# CPUWroom_Schem.net
KiCad netlist of a schematic drawn in Altium Designer
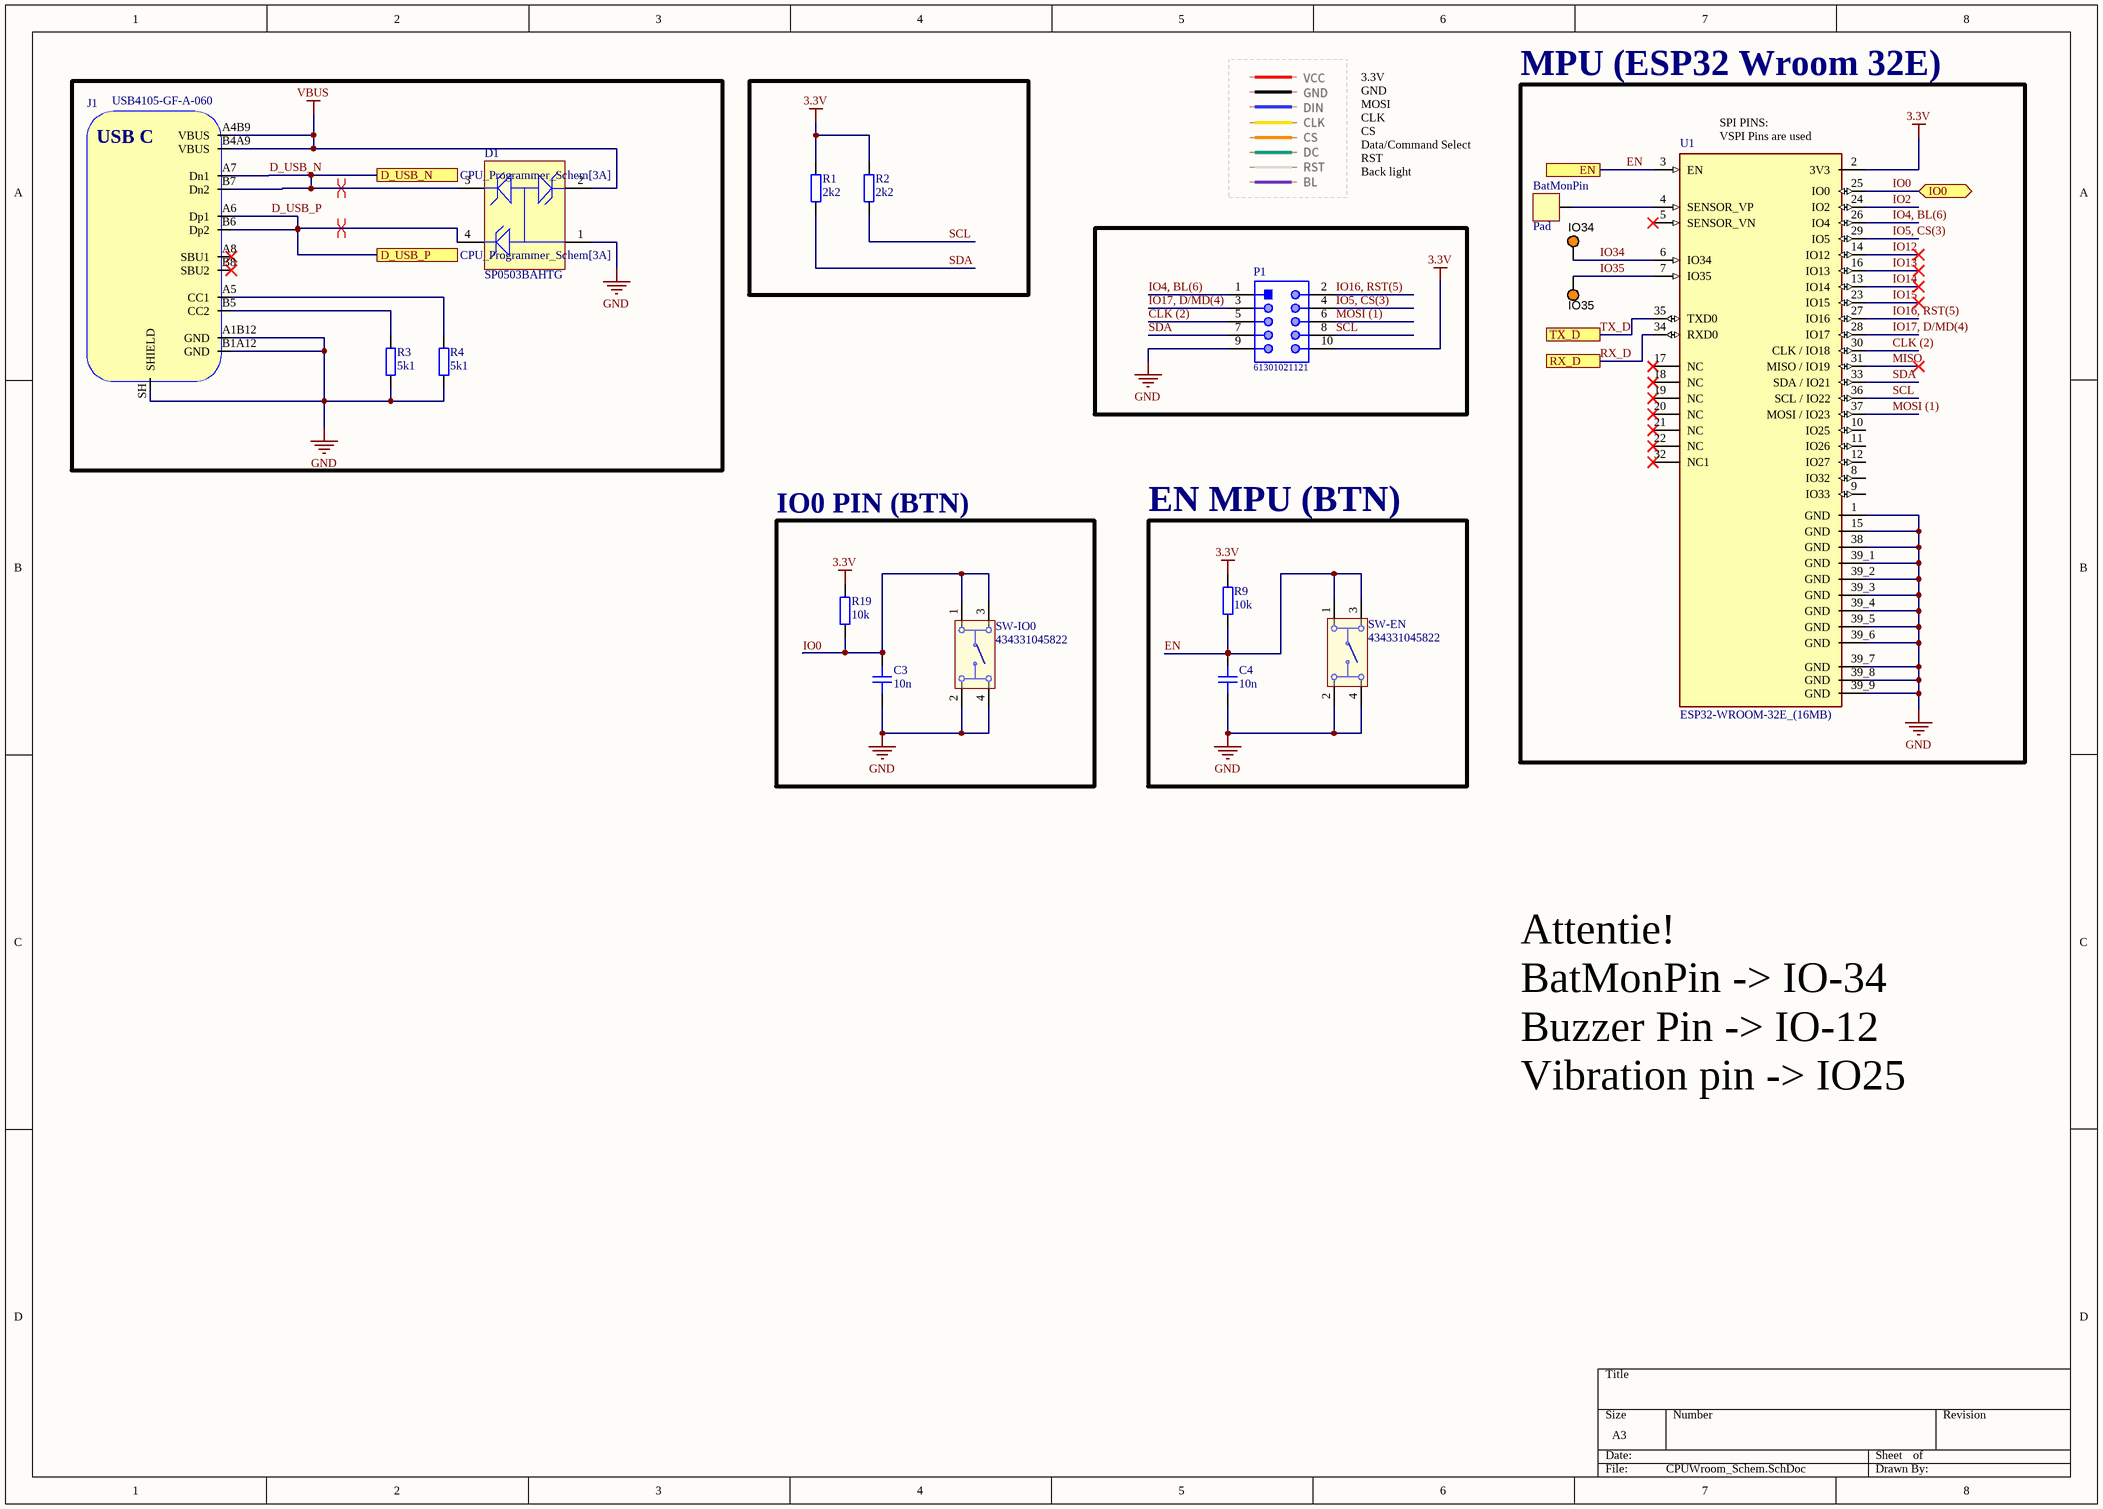
[diagram p0: CPUWroom_Schem.SchDoc]

(export (version "E")
  (design (tool "Eeschema 10.0.6"))
  (components
    (comp (ref "BatMonPin")
      (value "Pad")
      (footprint "PAD_SQ_2MM")
      (description "Test Point Square 2mm")
      (libsource (lib "Schem_Lib_DaanHeetkamp.") (part "PAD_SQ_2MM"))
    )
    (comp (ref "C3")
      (value "10n")
      (footprint "CAP_1206")
      (description "Capacitor SMD 1206 50V")
      (libsource (lib "Schem_Lib_DaanHeetkamp.") (part "CAP_1206_50V"))
    )
    (comp (ref "C4")
      (value "10n")
      (footprint "CAP_1206")
      (description "Capacitor SMD 1206 50V")
      (libsource (lib "Schem_Lib_DaanHeetkamp.") (part "CAP_1206_50V"))
    )
    (comp (ref "D1")
      (value "SP0503BAHTG")
      (footprint "LFUS-SOT143-4_V")
      (description "TVS Diode Array, 30 pF, 30 KV, -40 to 85 degC, 4-Pin SOT143, RoHS, Tape and Reel")
      (fields (field (name "MANUFACTURER") "Littelfuse"))
      (libsource (lib "Altium Content Vault") (part "LFUS-SP0503BAHTG-SOT143-4"))
    )
    (comp (ref "IO34")
      (value "5003")
      (footprint "KSTN-5003")
      (description "Test Point, Orange, Height 4.6 mm, Tail Length 3 mm, 1-Pin THD, RoHS")
      (fields (field (name "MANUFACTURER") "Keystone"))
      (libsource (lib "Saxion University of Applied Sciences") (part "TESTPOINT_ORANGE"))
    )
    (comp (ref "IO35")
      (value "5003")
      (footprint "KSTN-5003")
      (description "Test Point, Orange, Height 4.6 mm, Tail Length 3 mm, 1-Pin THD, RoHS")
      (fields (field (name "MANUFACTURER") "Keystone"))
      (libsource (lib "Saxion University of Applied Sciences") (part "TESTPOINT_ORANGE"))
    )
    (comp (ref "J1")
      (value "USB4105-GF-A-060")
      (footprint "USB4105-GF-A-060")
      (description "USB Connector Type C SMT 12 Pin")
      (fields (field (name "MANUFACTURER") "GCT"))
      (libsource (lib "Schem_Lib_DaanHeetkamp.") (part "USB4105-GF-A-060"))
    )
    (comp (ref "P1")
      (value "61301021121")
      (footprint "61301021121")
      (description "THT Vertical Pin Header WR-PHD, Pitch 2.54 mm, Dual Row, 10 pins")
      (fields (field (name "MANUFACTURER") "Wurth Elektronik") (field (name "PUBLISHER") "WurthElektronik"))
      (libsource (lib "Altium Content Vault") (part "WE-CN-2P-M-R10"))
    )
    (comp (ref "R1")
      (value "2k2")
      (footprint "RES_1206")
      (description "Resistor SMD 1206")
      (libsource (lib "Schem_Lib_DaanHeetkamp.") (part "RES_1206"))
    )
    (comp (ref "R2")
      (value "2k2")
      (footprint "RES_1206")
      (description "Resistor SMD 1206")
      (libsource (lib "Schem_Lib_DaanHeetkamp.") (part "RES_1206"))
    )
    (comp (ref "R3")
      (value "5k1")
      (footprint "RES_1206")
      (description "Resistor SMD 1206")
      (libsource (lib "Schem_Lib_DaanHeetkamp.") (part "RES_1206"))
    )
    (comp (ref "R4")
      (value "5k1")
      (footprint "RES_1206")
      (description "Resistor SMD 1206")
      (libsource (lib "Schem_Lib_DaanHeetkamp.") (part "RES_1206"))
    )
    (comp (ref "R9")
      (value "10k")
      (footprint "RES_1206")
      (description "Resistor SMD 1206")
      (libsource (lib "Schem_Lib_DaanHeetkamp.") (part "RES_1206"))
    )
    (comp (ref "R19")
      (value "10k")
      (footprint "RES_1206")
      (description "Resistor SMD 1206")
      (libsource (lib "Schem_Lib_DaanHeetkamp.") (part "RES_1206"))
    )
    (comp (ref "SW-EN")
      (value "434331045822")
      (footprint "434331045822")
      (description "WS-TASU SMD Tact Switch 4.7X3.5 mm side push")
      (fields (field (name "MANUFACTURER") "Wuerth Elektronik"))
      (libsource (lib "Altium Content Vault") (part "WE-TACT-SW-4"))
    )
    (comp (ref "SW-IO0")
      (value "434331045822")
      (footprint "434331045822")
      (description "WS-TASU SMD Tact Switch 4.7X3.5 mm side push")
      (fields (field (name "MANUFACTURER") "Wuerth Elektronik"))
      (libsource (lib "Altium Content Vault") (part "WE-TACT-SW-4"))
    )
    (comp (ref "U1")
      (value "ESP32-WROOM-32E_(16MB)")
      (footprint "XCVR_ESP32-WROOM-32E_(16MB)")
      (fields (field (name "MP") "ESP32-WROOM-32E (16MB)") (field (name "MF") "Espressif Systems"))
      (libsource (lib "Schem_Lib_DaanHeetkamp.") (part "ESP32-WROOM-32E_(16MB)"))
    )
  )
  (nets
    (net (code "1") (name "/CLK (2)") (class "Default")
      (node (ref "P1") (pin "5") (pinfunction "5_5") (pintype "passive"))
      (node (ref "U1") (pin "30") (pinfunction "CLK_/_IO18_30") (pintype "bidirectional"))
    )
    (net (code "2") (name "/D_USB_N") (class "Default")
      (node (ref "D1") (pin "3") (pinfunction "3_3") (pintype "passive"))
      (node (ref "J1") (pin "A7") (pinfunction "Dn1_A7") (pintype "passive"))
      (node (ref "J1") (pin "B7") (pinfunction "Dn2_B7") (pintype "passive"))
    )
    (net (code "3") (name "/D_USB_P") (class "Default")
      (node (ref "D1") (pin "4") (pinfunction "4_4") (pintype "passive"))
      (node (ref "J1") (pin "A6") (pinfunction "Dp1_A6") (pintype "passive"))
      (node (ref "J1") (pin "B6") (pinfunction "Dp2_B6") (pintype "passive"))
    )
    (net (code "4") (name "/EN") (class "Default")
      (node (ref "C4") (pin "2") (pinfunction "2_2") (pintype "passive"))
      (node (ref "R9") (pin "2") (pinfunction "2_2") (pintype "passive"))
      (node (ref "SW-EN") (pin "1") (pinfunction "1_1") (pintype "passive"))
      (node (ref "SW-EN") (pin "3") (pinfunction "3_3") (pintype "passive"))
      (node (ref "U1") (pin "3") (pinfunction "EN_3") (pintype "input"))
    )
    (net (code "5") (name "/IO0") (class "Default")
      (node (ref "C3") (pin "2") (pinfunction "2_2") (pintype "passive"))
      (node (ref "R19") (pin "2") (pinfunction "2_2") (pintype "passive"))
      (node (ref "SW-IO0") (pin "1") (pinfunction "1_1") (pintype "passive"))
      (node (ref "SW-IO0") (pin "3") (pinfunction "3_3") (pintype "passive"))
      (node (ref "U1") (pin "25") (pinfunction "IO0_25") (pintype "bidirectional"))
    )
    (net (code "6") (name "/IO2") (class "Default")
      (node (ref "U1") (pin "24") (pinfunction "IO2_24") (pintype "bidirectional"))
    )
    (net (code "7") (name "/IO4, BL(6)") (class "Default")
      (node (ref "P1") (pin "1") (pinfunction "1_1") (pintype "passive"))
      (node (ref "U1") (pin "26") (pinfunction "IO4_26") (pintype "bidirectional"))
    )
    (net (code "8") (name "/IO5, CS(3)") (class "Default")
      (node (ref "P1") (pin "4") (pinfunction "4_4") (pintype "passive"))
      (node (ref "U1") (pin "29") (pinfunction "IO5_29") (pintype "bidirectional"))
    )
    (net (code "9") (name "/IO12") (class "Default")
      (node (ref "U1") (pin "14") (pinfunction "IO12_14") (pintype "bidirectional+no_connect"))
    )
    (net (code "10") (name "/IO13") (class "Default")
      (node (ref "U1") (pin "16") (pinfunction "IO13_16") (pintype "bidirectional+no_connect"))
    )
    (net (code "11") (name "/IO14") (class "Default")
      (node (ref "U1") (pin "13") (pinfunction "IO14_13") (pintype "bidirectional+no_connect"))
    )
    (net (code "12") (name "/IO15") (class "Default")
      (node (ref "U1") (pin "23") (pinfunction "IO15_23") (pintype "bidirectional+no_connect"))
    )
    (net (code "13") (name "/IO16, RST(5)") (class "Default")
      (node (ref "P1") (pin "2") (pinfunction "2_2") (pintype "passive"))
      (node (ref "U1") (pin "27") (pinfunction "IO16_27") (pintype "bidirectional"))
    )
    (net (code "14") (name "/IO17, D{slash}MD(4)") (class "Default")
      (node (ref "P1") (pin "3") (pinfunction "3_3") (pintype "passive"))
      (node (ref "U1") (pin "28") (pinfunction "IO17_28") (pintype "bidirectional"))
    )
    (net (code "15") (name "/IO34") (class "Default")
      (node (ref "IO34") (pin "1") (pinfunction "1_1") (pintype "passive"))
      (node (ref "U1") (pin "6") (pinfunction "IO34_6") (pintype "input"))
    )
    (net (code "16") (name "/IO35") (class "Default")
      (node (ref "IO35") (pin "1") (pinfunction "1_1") (pintype "passive"))
      (node (ref "U1") (pin "7") (pinfunction "IO35_7") (pintype "input"))
    )
    (net (code "17") (name "/MISO") (class "Default")
      (node (ref "U1") (pin "31") (pinfunction "MISO_/_IO19_31") (pintype "bidirectional+no_connect"))
    )
    (net (code "18") (name "/MOSI (1)") (class "Default")
      (node (ref "P1") (pin "6") (pinfunction "6_6") (pintype "passive"))
      (node (ref "U1") (pin "37") (pinfunction "MOSI_/_IO23_37") (pintype "bidirectional"))
    )
    (net (code "19") (name "/RX_D") (class "Default")
      (node (ref "U1") (pin "34") (pinfunction "RXD0_34") (pintype "bidirectional"))
    )
    (net (code "20") (name "/SCL") (class "Default")
      (node (ref "P1") (pin "8") (pinfunction "8_8") (pintype "passive"))
      (node (ref "R2") (pin "2") (pinfunction "2_2") (pintype "passive"))
      (node (ref "U1") (pin "36") (pinfunction "SCL_/_IO22_36") (pintype "bidirectional"))
    )
    (net (code "21") (name "/SDA") (class "Default")
      (node (ref "P1") (pin "7") (pinfunction "7_7") (pintype "passive"))
      (node (ref "R1") (pin "2") (pinfunction "2_2") (pintype "passive"))
      (node (ref "U1") (pin "33") (pinfunction "SDA_/_IO21_33") (pintype "bidirectional"))
    )
    (net (code "22") (name "/TX_D") (class "Default")
      (node (ref "U1") (pin "35") (pinfunction "TXD0_35") (pintype "bidirectional"))
    )
    (net (code "23") (name "3.3V") (class "Default")
      (node (ref "P1") (pin "10") (pinfunction "10_10") (pintype "passive"))
      (node (ref "R1") (pin "1") (pinfunction "1_1") (pintype "passive"))
      (node (ref "R19") (pin "1") (pinfunction "1_1") (pintype "passive"))
      (node (ref "R2") (pin "1") (pinfunction "1_1") (pintype "passive"))
      (node (ref "R9") (pin "1") (pinfunction "1_1") (pintype "passive"))
      (node (ref "U1") (pin "2") (pinfunction "3V3_2") (pintype "power_in"))
    )
    (net (code "24") (name "GND") (class "Default")
      (node (ref "C3") (pin "1") (pinfunction "1_1") (pintype "passive"))
      (node (ref "C4") (pin "1") (pinfunction "1_1") (pintype "passive"))
      (node (ref "D1") (pin "1") (pinfunction "1_1") (pintype "passive"))
      (node (ref "J1") (pin "A1B12") (pinfunction "GND_A1B12") (pintype "passive"))
      (node (ref "J1") (pin "B1A12") (pinfunction "GND_B1A12") (pintype "passive"))
      (node (ref "J1") (pin "SH") (pinfunction "SHIELD_SH") (pintype "passive"))
      (node (ref "P1") (pin "9") (pinfunction "9_9") (pintype "passive"))
      (node (ref "R3") (pin "1") (pinfunction "1_1") (pintype "passive"))
      (node (ref "R4") (pin "1") (pinfunction "1_1") (pintype "passive"))
      (node (ref "SW-EN") (pin "2") (pinfunction "2_2") (pintype "passive"))
      (node (ref "SW-EN") (pin "4") (pinfunction "4_4") (pintype "passive"))
      (node (ref "SW-IO0") (pin "2") (pinfunction "2_2") (pintype "passive"))
      (node (ref "SW-IO0") (pin "4") (pinfunction "4_4") (pintype "passive"))
      (node (ref "U1") (pin "1") (pinfunction "GND_1") (pintype "power_in"))
      (node (ref "U1") (pin "15") (pinfunction "GND_15") (pintype "power_in"))
      (node (ref "U1") (pin "38") (pinfunction "GND_38") (pintype "power_in"))
      (node (ref "U1") (pin "39_1") (pinfunction "GND_39_1") (pintype "power_in"))
      (node (ref "U1") (pin "39_2") (pinfunction "GND_39_2") (pintype "power_in"))
      (node (ref "U1") (pin "39_3") (pinfunction "GND_39_3") (pintype "power_in"))
      (node (ref "U1") (pin "39_4") (pinfunction "GND_39_4") (pintype "power_in"))
      (node (ref "U1") (pin "39_5") (pinfunction "GND_39_5") (pintype "power_in"))
      (node (ref "U1") (pin "39_6") (pinfunction "GND_39_6") (pintype "power_in"))
      (node (ref "U1") (pin "39_7") (pinfunction "GND_39_7") (pintype "power_in"))
      (node (ref "U1") (pin "39_8") (pinfunction "GND_39_8") (pintype "power_in"))
      (node (ref "U1") (pin "39_9") (pinfunction "GND_39_9") (pintype "power_in"))
    )
    (net (code "25") (name "Net-(J1-CC1)") (class "Default")
      (node (ref "J1") (pin "A5") (pinfunction "CC1_A5") (pintype "passive"))
      (node (ref "R4") (pin "2") (pinfunction "2_2") (pintype "passive"))
    )
    (net (code "26") (name "Net-(J1-CC2)") (class "Default")
      (node (ref "J1") (pin "B5") (pinfunction "CC2_B5") (pintype "passive"))
      (node (ref "R3") (pin "2") (pinfunction "2_2") (pintype "passive"))
    )
    (net (code "27") (name "Net-(U1-SENSOR_VP)") (class "Default")
      (node (ref "BatMonPin") (pin "1") (pinfunction "1_1") (pintype "passive"))
      (node (ref "U1") (pin "4") (pinfunction "SENSOR_VP_4") (pintype "input"))
    )
    (net (code "28") (name "VBUS") (class "Default")
      (node (ref "D1") (pin "2") (pinfunction "2_2") (pintype "passive"))
      (node (ref "J1") (pin "A4B9") (pinfunction "VBUS_A4B9") (pintype "passive"))
      (node (ref "J1") (pin "B4A9") (pinfunction "VBUS_B4A9") (pintype "passive"))
    )
    (net (code "29") (name "unconnected-(J1-SBU1-PadA8)") (class "Default")
      (node (ref "J1") (pin "A8") (pinfunction "SBU1_A8") (pintype "passive+no_connect"))
    )
    (net (code "30") (name "unconnected-(J1-SBU2-PadB8)") (class "Default")
      (node (ref "J1") (pin "B8") (pinfunction "SBU2_B8") (pintype "passive+no_connect"))
    )
    (net (code "31") (name "unconnected-(U1-IO25-Pad10)") (class "Default")
      (node (ref "U1") (pin "10") (pinfunction "IO25_10") (pintype "bidirectional"))
    )
    (net (code "32") (name "unconnected-(U1-IO26-Pad11)") (class "Default")
      (node (ref "U1") (pin "11") (pinfunction "IO26_11") (pintype "bidirectional"))
    )
    (net (code "33") (name "unconnected-(U1-IO27-Pad12)") (class "Default")
      (node (ref "U1") (pin "12") (pinfunction "IO27_12") (pintype "bidirectional"))
    )
    (net (code "34") (name "unconnected-(U1-IO32-Pad8)") (class "Default")
      (node (ref "U1") (pin "8") (pinfunction "IO32_8") (pintype "bidirectional"))
    )
    (net (code "35") (name "unconnected-(U1-IO33-Pad9)") (class "Default")
      (node (ref "U1") (pin "9") (pinfunction "IO33_9") (pintype "bidirectional"))
    )
    (net (code "36") (name "unconnected-(U1-NC-Pad17)") (class "Default")
      (node (ref "U1") (pin "17") (pinfunction "NC_17") (pintype "passive+no_connect"))
    )
    (net (code "37") (name "unconnected-(U1-NC-Pad18)") (class "Default")
      (node (ref "U1") (pin "18") (pinfunction "NC_18") (pintype "passive+no_connect"))
    )
    (net (code "38") (name "unconnected-(U1-NC-Pad19)") (class "Default")
      (node (ref "U1") (pin "19") (pinfunction "NC_19") (pintype "passive+no_connect"))
    )
    (net (code "39") (name "unconnected-(U1-NC-Pad20)") (class "Default")
      (node (ref "U1") (pin "20") (pinfunction "NC_20") (pintype "passive+no_connect"))
    )
    (net (code "40") (name "unconnected-(U1-NC-Pad21)") (class "Default")
      (node (ref "U1") (pin "21") (pinfunction "NC_21") (pintype "passive+no_connect"))
    )
    (net (code "41") (name "unconnected-(U1-NC-Pad22)") (class "Default")
      (node (ref "U1") (pin "22") (pinfunction "NC_22") (pintype "passive+no_connect"))
    )
    (net (code "42") (name "unconnected-(U1-NC1-Pad32)") (class "Default")
      (node (ref "U1") (pin "32") (pinfunction "NC1_32") (pintype "passive+no_connect"))
    )
    (net (code "43") (name "unconnected-(U1-SENSOR_VN-Pad5)") (class "Default")
      (node (ref "U1") (pin "5") (pinfunction "SENSOR_VN_5") (pintype "input+no_connect"))
    )
  )
)
